# USB-Interface_V1_1.net
KiCad netlist of a schematic drawn in EAGLE
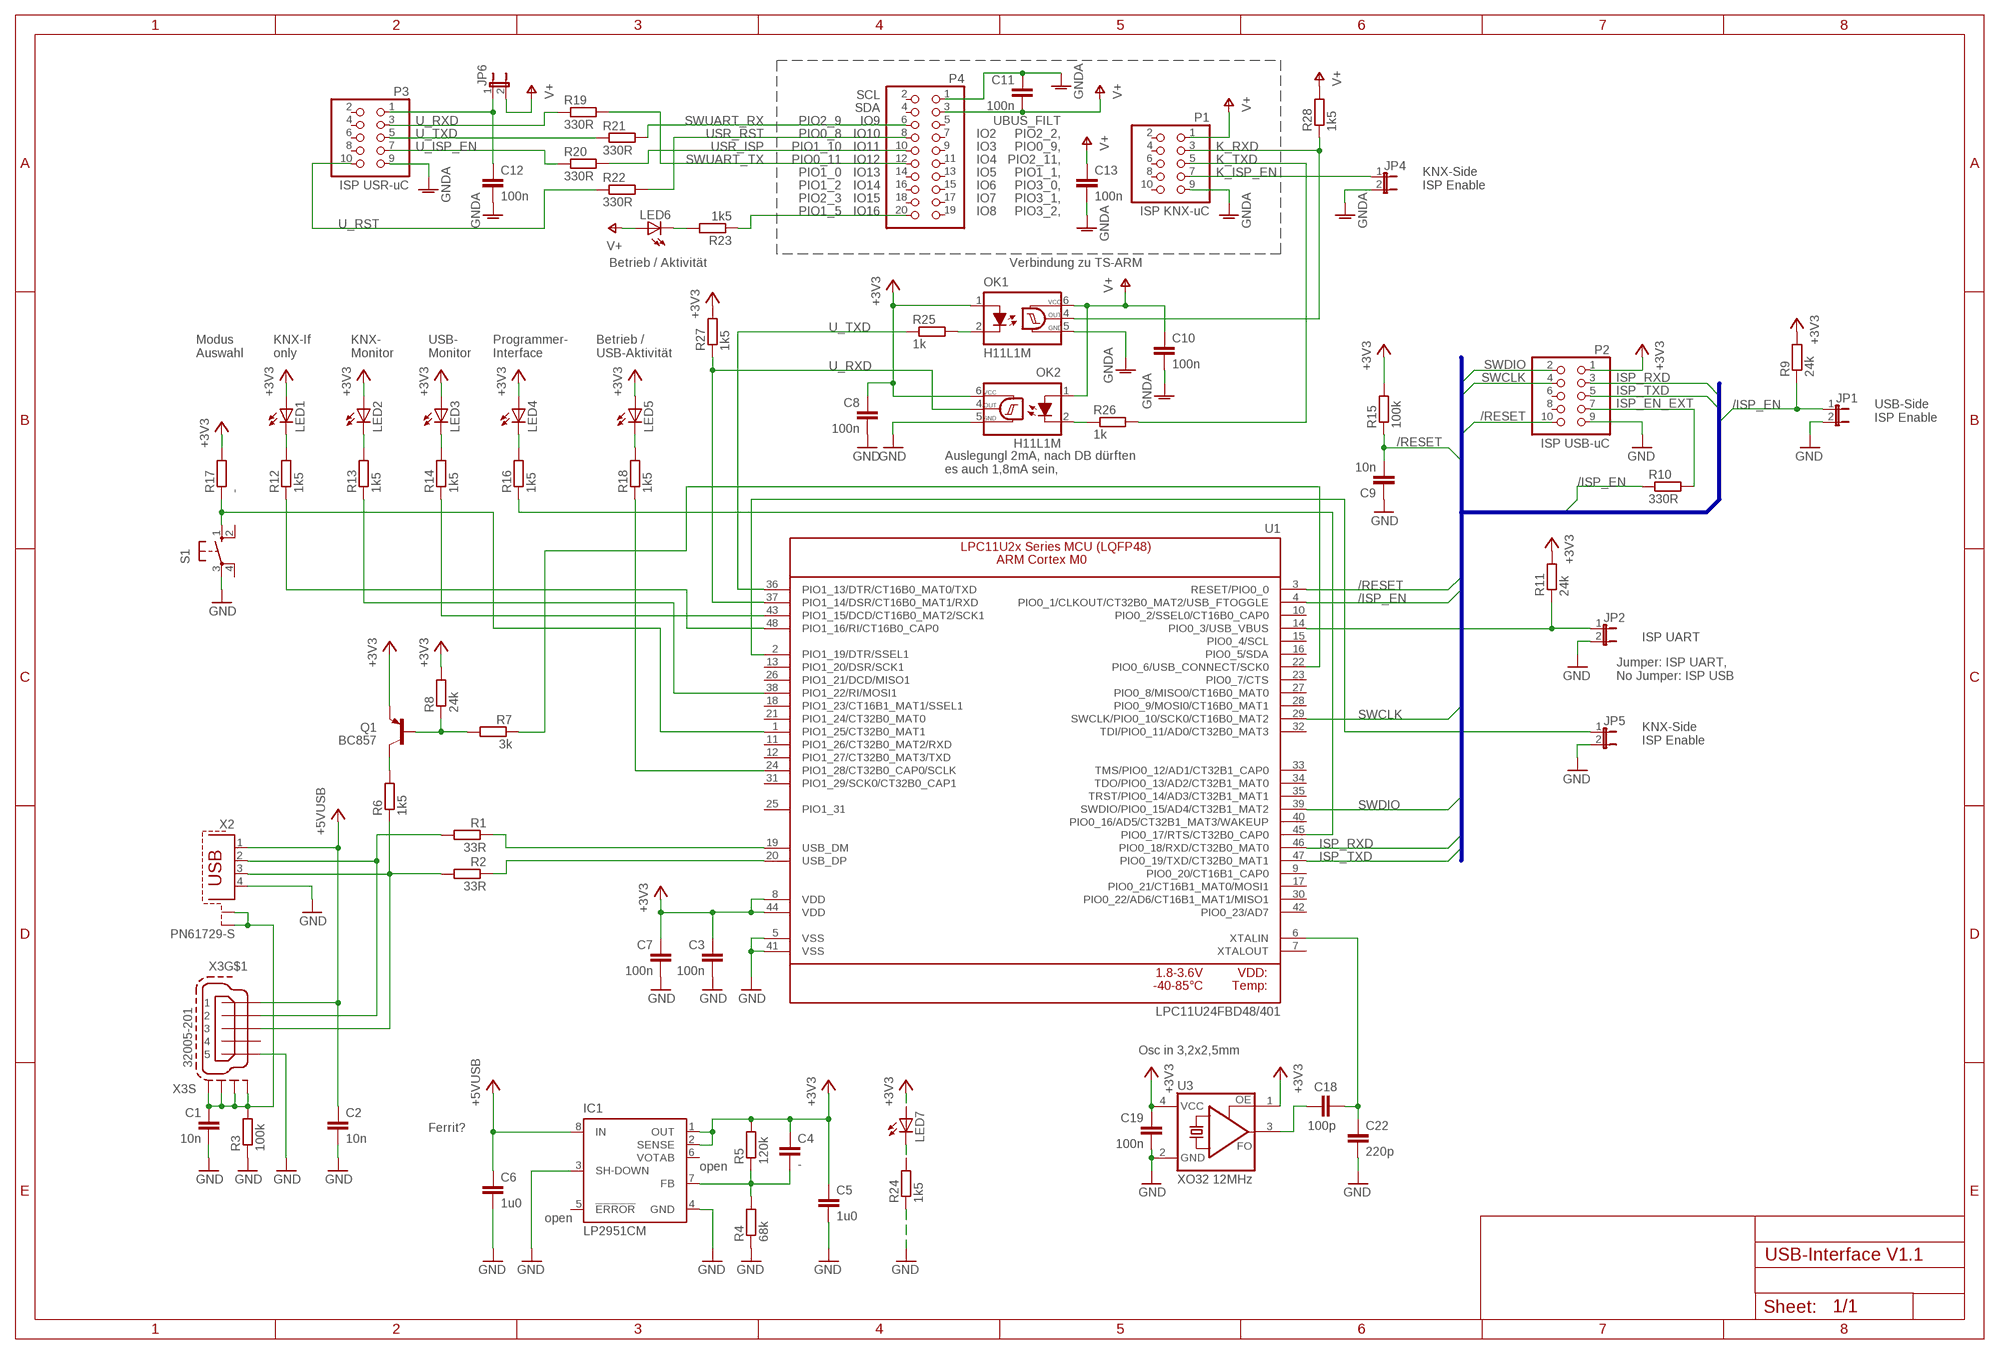
[diagram p0: schematic, sheet 1]

(export (version "E")
  (design (tool "Eeschema 10.0.6"))
  (components
    (comp (ref "C1")
      (value "10n")
      (footprint "eagle-import:R0805M")
      (libsource (lib "eagle-import") (part "C-EUC0805M"))
    )
    (comp (ref "C2")
      (value "10n")
      (footprint "eagle-import:R0805M")
      (libsource (lib "eagle-import") (part "C-EUC0805M"))
    )
    (comp (ref "C3")
      (value "100n")
      (footprint "eagle-import:R0805M")
      (libsource (lib "eagle-import") (part "C-EUC0805M"))
    )
    (comp (ref "C4")
      (value "-")
      (footprint "eagle-import:R0805M")
      (libsource (lib "eagle-import") (part "C-EUC0805M"))
    )
    (comp (ref "C5")
      (value "1u0")
      (footprint "eagle-import:R0805M")
      (libsource (lib "eagle-import") (part "C-EUC0805M"))
    )
    (comp (ref "C6")
      (value "1u0")
      (footprint "eagle-import:R0805M")
      (libsource (lib "eagle-import") (part "C-EUC0805M"))
    )
    (comp (ref "C7")
      (value "100n")
      (footprint "eagle-import:R0805M")
      (libsource (lib "eagle-import") (part "C-EUC0805M"))
    )
    (comp (ref "C8")
      (value "100n")
      (footprint "eagle-import:R0805M")
      (libsource (lib "eagle-import") (part "C-EUC0805M"))
    )
    (comp (ref "C9")
      (value "10n")
      (footprint "eagle-import:R0805M")
      (libsource (lib "eagle-import") (part "C-EUC0805M"))
    )
    (comp (ref "C10")
      (value "100n")
      (footprint "eagle-import:R0805M")
      (libsource (lib "eagle-import") (part "C-EUC0805M"))
    )
    (comp (ref "C11")
      (value "100n")
      (footprint "eagle-import:R0805M")
      (libsource (lib "eagle-import") (part "C-EUC0805M"))
    )
    (comp (ref "C12")
      (value "100n")
      (footprint "eagle-import:R0805M")
      (libsource (lib "eagle-import") (part "C-EUC0805M"))
    )
    (comp (ref "C13")
      (value "100n")
      (footprint "eagle-import:R0805M")
      (libsource (lib "eagle-import") (part "C-EUC0805M"))
    )
    (comp (ref "C18")
      (value "100p")
      (footprint "eagle-import:R0805M")
      (libsource (lib "eagle-import") (part "C-EUC0805M"))
    )
    (comp (ref "C19")
      (value "100n")
      (footprint "eagle-import:R0805M")
      (libsource (lib "eagle-import") (part "C-EUC0805M"))
    )
    (comp (ref "C22")
      (value "220p")
      (footprint "eagle-import:R0805M")
      (libsource (lib "eagle-import") (part "C-EUC0805M"))
    )
    (comp (ref "IC1")
      (value "LP2951CM")
      (footprint "eagle-import:SO08")
      (libsource (lib "eagle-import") (part "LP2951D"))
    )
    (comp (ref "JP1")
      (value "JP1E")
      (footprint "eagle-import:JP1")
      (libsource (lib "eagle-import") (part "JP1E"))
    )
    (comp (ref "JP2")
      (value "JP1E")
      (footprint "eagle-import:JP1")
      (libsource (lib "eagle-import") (part "JP1E"))
    )
    (comp (ref "JP4")
      (value "JP1E")
      (footprint "eagle-import:JP1")
      (libsource (lib "eagle-import") (part "JP1E"))
    )
    (comp (ref "JP5")
      (value "JP1E")
      (footprint "eagle-import:JP1")
      (libsource (lib "eagle-import") (part "JP1E"))
    )
    (comp (ref "JP6")
      (value "JP1E")
      (footprint "eagle-import:JP1")
      (libsource (lib "eagle-import") (part "JP1E"))
    )
    (comp (ref "LED1")
      (value "LEDSMT1206")
      (footprint "eagle-import:1206")
      (libsource (lib "eagle-import") (part "LEDSMT1206"))
    )
    (comp (ref "LED2")
      (value "LEDSMT1206")
      (footprint "eagle-import:1206")
      (libsource (lib "eagle-import") (part "LEDSMT1206"))
    )
    (comp (ref "LED3")
      (value "LEDSMT1206")
      (footprint "eagle-import:1206")
      (libsource (lib "eagle-import") (part "LEDSMT1206"))
    )
    (comp (ref "LED4")
      (value "LEDSMT1206")
      (footprint "eagle-import:1206")
      (libsource (lib "eagle-import") (part "LEDSMT1206"))
    )
    (comp (ref "LED5")
      (value "LEDSMT1206")
      (footprint "eagle-import:1206")
      (libsource (lib "eagle-import") (part "LEDSMT1206"))
    )
    (comp (ref "LED6")
      (value "LEDSMT1206")
      (footprint "eagle-import:1206")
      (libsource (lib "eagle-import") (part "LEDSMT1206"))
    )
    (comp (ref "LED7")
      (value "LEDSMT1206")
      (footprint "eagle-import:1206")
      (libsource (lib "eagle-import") (part "LEDSMT1206"))
    )
    (comp (ref "OK1")
      (value "H11L1M")
      (footprint "eagle-import:DIL06S")
      (libsource (lib "eagle-import") (part "H11LMM"))
    )
    (comp (ref "OK2")
      (value "H11L1M")
      (footprint "eagle-import:DIL06S")
      (libsource (lib "eagle-import") (part "H11LMM"))
    )
    (comp (ref "P1")
      (value "ISP KNX-uC")
      (footprint "eagle-import:2X05M")
      (libsource (lib "eagle-import") (part "PINHD-2X05_2.00"))
    )
    (comp (ref "P2")
      (value "ISP USB-uC")
      (footprint "eagle-import:2X05M")
      (libsource (lib "eagle-import") (part "PINHD-2X05_2.00"))
    )
    (comp (ref "P3")
      (value "ISP USR-uC")
      (footprint "eagle-import:2X05M")
      (libsource (lib "eagle-import") (part "PINHD-2X05_2.00"))
    )
    (comp (ref "P4")
      (value "PINHD-2X10/90")
      (footprint "eagle-import:2X10_90")
      (libsource (lib "eagle-import") (part "PINHD-2X10/90"))
    )
    (comp (ref "Q1")
      (value "BC857")
      (footprint "eagle-import:SOT23-BEC")
      (libsource (lib "eagle-import") (part "BC857SMDA"))
    )
    (comp (ref "R1")
      (value "33R")
      (footprint "eagle-import:R0805M")
      (libsource (lib "eagle-import") (part "R-EU_R0805M"))
    )
    (comp (ref "R2")
      (value "33R")
      (footprint "eagle-import:R0805M")
      (libsource (lib "eagle-import") (part "R-EU_R0805M"))
    )
    (comp (ref "R3")
      (value "100k")
      (footprint "eagle-import:R0805M")
      (libsource (lib "eagle-import") (part "R-EU_R0805M"))
    )
    (comp (ref "R4")
      (value "68k")
      (footprint "eagle-import:R0805M")
      (libsource (lib "eagle-import") (part "R-EU_R0805M"))
    )
    (comp (ref "R5")
      (value "120k")
      (footprint "eagle-import:R0805M")
      (libsource (lib "eagle-import") (part "R-EU_R0805M"))
    )
    (comp (ref "R6")
      (value "1k5")
      (footprint "eagle-import:R0805M")
      (libsource (lib "eagle-import") (part "R-EU_R0805M"))
    )
    (comp (ref "R7")
      (value "3k")
      (footprint "eagle-import:R0805M")
      (libsource (lib "eagle-import") (part "R-EU_R0805M"))
    )
    (comp (ref "R8")
      (value "24k")
      (footprint "eagle-import:R0805M")
      (libsource (lib "eagle-import") (part "R-EU_R0805M"))
    )
    (comp (ref "R9")
      (value "24k")
      (footprint "eagle-import:R0805M")
      (libsource (lib "eagle-import") (part "R-EU_R0805M"))
    )
    (comp (ref "R10")
      (value "330R")
      (footprint "eagle-import:R0805M")
      (libsource (lib "eagle-import") (part "R-EU_R0805M"))
    )
    (comp (ref "R11")
      (value "24k")
      (footprint "eagle-import:R0805M")
      (libsource (lib "eagle-import") (part "R-EU_R0805M"))
    )
    (comp (ref "R12")
      (value "1k5")
      (footprint "eagle-import:R0805M")
      (libsource (lib "eagle-import") (part "R-EU_R0805M"))
    )
    (comp (ref "R13")
      (value "1k5")
      (footprint "eagle-import:R0805M")
      (libsource (lib "eagle-import") (part "R-EU_R0805M"))
    )
    (comp (ref "R14")
      (value "1k5")
      (footprint "eagle-import:R0805M")
      (libsource (lib "eagle-import") (part "R-EU_R0805M"))
    )
    (comp (ref "R15")
      (value "100k")
      (footprint "eagle-import:R0805M")
      (libsource (lib "eagle-import") (part "R-EU_R0805M"))
    )
    (comp (ref "R16")
      (value "1k5")
      (footprint "eagle-import:R0805M")
      (libsource (lib "eagle-import") (part "R-EU_R0805M"))
    )
    (comp (ref "R17")
      (value "-")
      (footprint "eagle-import:R0805M")
      (libsource (lib "eagle-import") (part "R-EU_R0805M"))
    )
    (comp (ref "R18")
      (value "1k5")
      (footprint "eagle-import:R0805M")
      (libsource (lib "eagle-import") (part "R-EU_R0805M"))
    )
    (comp (ref "R19")
      (value "330R")
      (footprint "eagle-import:R0805M")
      (libsource (lib "eagle-import") (part "R-EU_R0805M"))
    )
    (comp (ref "R20")
      (value "330R")
      (footprint "eagle-import:R0805M")
      (libsource (lib "eagle-import") (part "R-EU_R0805M"))
    )
    (comp (ref "R21")
      (value "330R")
      (footprint "eagle-import:R0805M")
      (libsource (lib "eagle-import") (part "R-EU_R0805M"))
    )
    (comp (ref "R22")
      (value "330R")
      (footprint "eagle-import:R0805M")
      (libsource (lib "eagle-import") (part "R-EU_R0805M"))
    )
    (comp (ref "R23")
      (value "1k5")
      (footprint "eagle-import:R0805M")
      (libsource (lib "eagle-import") (part "R-EU_R0805M"))
    )
    (comp (ref "R24")
      (value "1k5")
      (footprint "eagle-import:R0805M")
      (libsource (lib "eagle-import") (part "R-EU_R0805M"))
    )
    (comp (ref "R25")
      (value "1k")
      (footprint "eagle-import:R0805M")
      (libsource (lib "eagle-import") (part "R-EU_R0805M"))
    )
    (comp (ref "R26")
      (value "1k")
      (footprint "eagle-import:R0805M")
      (libsource (lib "eagle-import") (part "R-EU_R0805M"))
    )
    (comp (ref "R27")
      (value "1k5")
      (footprint "eagle-import:R0805M")
      (libsource (lib "eagle-import") (part "R-EU_R0805M"))
    )
    (comp (ref "R28")
      (value "1k5")
      (footprint "eagle-import:R0805M")
      (libsource (lib "eagle-import") (part "R-EU_R0805M"))
    )
    (comp (ref "S1")
      (value "10-XXSMD")
      (footprint "eagle-import:B3F-10XX_SMD")
      (libsource (lib "eagle-import") (part "10-XXSMD"))
    )
    (comp (ref "U1")
      (value "LPC11U24FBD48/401")
      (footprint "eagle-import:LQFP48")
      (libsource (lib "eagle-import") (part "LPC11U24FBD48"))
    )
    (comp (ref "U3")
      (value "XO32 12MHz")
      (footprint "eagle-import:ASF")
      (libsource (lib "eagle-import") (part "ASFL"))
    )
    (comp (ref "X2")
      (value "PN61729-S")
      (footprint "eagle-import:PN61729-S")
      (libsource (lib "eagle-import") (part "PN61729-S"))
    )
    (comp (ref "X3")
      (value "32005-201")
      (footprint "eagle-import:32005-201")
      (libsource (lib "eagle-import") (part "MINI-USB-SCHIELD-32005-201"))
    )
  )
  (nets
    (net (code "1") (name "+3V3") (class "Default")
      (node (ref "C19") (pin "1") (pinfunction "1_1") (pintype "passive"))
      (node (ref "C3") (pin "1") (pinfunction "1_1") (pintype "passive"))
      (node (ref "C4") (pin "1") (pinfunction "1_1") (pintype "passive"))
      (node (ref "C5") (pin "1") (pinfunction "1_1") (pintype "passive"))
      (node (ref "C7") (pin "1") (pinfunction "1_1") (pintype "passive"))
      (node (ref "C8") (pin "1") (pinfunction "1_1") (pintype "passive"))
      (node (ref "IC1") (pin "1") (pinfunction "OUT_1") (pintype "input"))
      (node (ref "IC1") (pin "2") (pinfunction "SENSE_2") (pintype "input"))
      (node (ref "LED1") (pin "A") (pinfunction "A_A") (pintype "passive"))
      (node (ref "LED2") (pin "A") (pinfunction "A_A") (pintype "passive"))
      (node (ref "LED3") (pin "A") (pinfunction "A_A") (pintype "passive"))
      (node (ref "LED4") (pin "A") (pinfunction "A_A") (pintype "passive"))
      (node (ref "LED5") (pin "A") (pinfunction "A_A") (pintype "passive"))
      (node (ref "LED7") (pin "A") (pinfunction "A_A") (pintype "passive"))
      (node (ref "OK1") (pin "1") (pinfunction "A_1") (pintype "passive"))
      (node (ref "OK2") (pin "6") (pinfunction "VCC_6") (pintype "power_in"))
      (node (ref "P2") (pin "1") (pinfunction "1_1") (pintype "passive"))
      (node (ref "Q1") (pin "E") (pinfunction "E_E") (pintype "passive"))
      (node (ref "R11") (pin "2") (pinfunction "2_2") (pintype "passive"))
      (node (ref "R15") (pin "2") (pinfunction "2_2") (pintype "passive"))
      (node (ref "R17") (pin "2") (pinfunction "2_2") (pintype "passive"))
      (node (ref "R27") (pin "2") (pinfunction "2_2") (pintype "passive"))
      (node (ref "R5") (pin "2") (pinfunction "2_2") (pintype "passive"))
      (node (ref "R8") (pin "2") (pinfunction "2_2") (pintype "passive"))
      (node (ref "R9") (pin "2") (pinfunction "2_2") (pintype "passive"))
      (node (ref "U1") (pin "44") (pinfunction "VDD_44") (pintype "power_in"))
      (node (ref "U1") (pin "8") (pinfunction "VDD_8") (pintype "power_in"))
      (node (ref "U3") (pin "1") (pinfunction "OE_1") (pintype "input"))
      (node (ref "U3") (pin "4") (pinfunction "VCC_4") (pintype "power_in"))
    )
    (net (code "2") (name "+5VUSB") (class "Default")
      (node (ref "C2") (pin "1") (pinfunction "1_1") (pintype "passive"))
      (node (ref "C6") (pin "1") (pinfunction "1_1") (pintype "passive"))
      (node (ref "IC1") (pin "8") (pinfunction "IN_8") (pintype "input"))
      (node (ref "X2") (pin "1") (pinfunction "1_1") (pintype "passive"))
      (node (ref "X3") (pin "1") (pinfunction "1_1") (pintype "passive"))
    )
    (net (code "3") (name "/ISP_EN_EXT") (class "Default")
      (node (ref "P2") (pin "7") (pinfunction "7_7") (pintype "passive"))
      (node (ref "R10") (pin "2") (pinfunction "2_2") (pintype "passive"))
    )
    (net (code "4") (name "/ISP_RXD") (class "Default")
      (node (ref "P2") (pin "3") (pinfunction "3_3") (pintype "passive"))
      (node (ref "U1") (pin "46") (pinfunction "PIO0_18/RXD/CT32B0_MAT0_46") (pintype "bidirectional"))
    )
    (net (code "5") (name "/ISP_TXD") (class "Default")
      (node (ref "P2") (pin "5") (pinfunction "5_5") (pintype "passive"))
      (node (ref "U1") (pin "47") (pinfunction "PIO0_19/TXD/CT32B0_MAT1_47") (pintype "bidirectional"))
    )
    (net (code "6") (name "/K_ISP_EN") (class "Default")
      (node (ref "JP4") (pin "1") (pinfunction "1_1") (pintype "passive"))
      (node (ref "P1") (pin "7") (pinfunction "7_7") (pintype "passive"))
    )
    (net (code "7") (name "/K_RXD") (class "Default")
      (node (ref "OK1") (pin "4") (pinfunction "OUT_4") (pintype "output"))
      (node (ref "P1") (pin "3") (pinfunction "3_3") (pintype "passive"))
      (node (ref "R28") (pin "1") (pinfunction "1_1") (pintype "passive"))
    )
    (net (code "8") (name "/K_TXD") (class "Default")
      (node (ref "P1") (pin "5") (pinfunction "5_5") (pintype "passive"))
      (node (ref "R26") (pin "2") (pinfunction "2_2") (pintype "passive"))
    )
    (net (code "9") (name "/SWCLK") (class "Default")
      (node (ref "P2") (pin "4") (pinfunction "4_4") (pintype "passive"))
      (node (ref "U1") (pin "29") (pinfunction "SWCLK/PIO0_10/SCK0/CT16B0_MAT2_29") (pintype "bidirectional"))
    )
    (net (code "10") (name "/SWDIO") (class "Default")
      (node (ref "P2") (pin "2") (pinfunction "2_2") (pintype "passive"))
      (node (ref "U1") (pin "39") (pinfunction "SWDIO/PIO0_15/AD4/CT32B1_MAT2_39") (pintype "bidirectional"))
    )
    (net (code "11") (name "/SWUART_RX") (class "Default")
      (node (ref "P4") (pin "6") (pinfunction "6_6") (pintype "passive"))
      (node (ref "R21") (pin "2") (pinfunction "2_2") (pintype "passive"))
    )
    (net (code "12") (name "/SWUART_TX") (class "Default")
      (node (ref "P4") (pin "12") (pinfunction "12_12") (pintype "passive"))
      (node (ref "R19") (pin "2") (pinfunction "2_2") (pintype "passive"))
    )
    (net (code "13") (name "/USR_ISP") (class "Default")
      (node (ref "P4") (pin "10") (pinfunction "10_10") (pintype "passive"))
      (node (ref "R20") (pin "2") (pinfunction "2_2") (pintype "passive"))
    )
    (net (code "14") (name "/USR_RST") (class "Default")
      (node (ref "P4") (pin "8") (pinfunction "8_8") (pintype "passive"))
      (node (ref "R22") (pin "2") (pinfunction "2_2") (pintype "passive"))
    )
    (net (code "15") (name "/U_RXD") (class "Default")
      (node (ref "OK2") (pin "4") (pinfunction "OUT_4") (pintype "output"))
      (node (ref "R27") (pin "1") (pinfunction "1_1") (pintype "passive"))
      (node (ref "U1") (pin "37") (pinfunction "PIO1_14/DSR/CT16B0_MAT1/RXD_37") (pintype "bidirectional"))
    )
    (net (code "16") (name "/U_TXD") (class "Default")
      (node (ref "R25") (pin "1") (pinfunction "1_1") (pintype "passive"))
      (node (ref "U1") (pin "36") (pinfunction "PIO1_13/DTR/CT16B0_MAT0/TXD_36") (pintype "bidirectional"))
    )
    (net (code "17") (name "/{slash}ISP_EN") (class "Default")
      (node (ref "JP1") (pin "1") (pinfunction "1_1") (pintype "passive"))
      (node (ref "R10") (pin "1") (pinfunction "1_1") (pintype "passive"))
      (node (ref "R9") (pin "1") (pinfunction "1_1") (pintype "passive"))
      (node (ref "U1") (pin "4") (pinfunction "PIO0_1/CLKOUT/CT32B0_MAT2/USB_FTOGGLE_4") (pintype "bidirectional"))
    )
    (net (code "18") (name "/{slash}RESET") (class "Default")
      (node (ref "C9") (pin "2") (pinfunction "2_2") (pintype "passive"))
      (node (ref "P2") (pin "10") (pinfunction "10_10") (pintype "passive"))
      (node (ref "R15") (pin "1") (pinfunction "1_1") (pintype "passive"))
      (node (ref "U1") (pin "3") (pinfunction "RESET/PIO0_0_3") (pintype "bidirectional"))
    )
    (net (code "19") (name "GND") (class "Default")
      (node (ref "C1") (pin "2") (pinfunction "2_2") (pintype "passive"))
      (node (ref "C19") (pin "2") (pinfunction "2_2") (pintype "passive"))
      (node (ref "C2") (pin "2") (pinfunction "2_2") (pintype "passive"))
      (node (ref "C22") (pin "2") (pinfunction "2_2") (pintype "passive"))
      (node (ref "C3") (pin "2") (pinfunction "2_2") (pintype "passive"))
      (node (ref "C5") (pin "2") (pinfunction "2_2") (pintype "passive"))
      (node (ref "C6") (pin "2") (pinfunction "2_2") (pintype "passive"))
      (node (ref "C7") (pin "2") (pinfunction "2_2") (pintype "passive"))
      (node (ref "C8") (pin "2") (pinfunction "2_2") (pintype "passive"))
      (node (ref "C9") (pin "1") (pinfunction "1_1") (pintype "passive"))
      (node (ref "IC1") (pin "3") (pinfunction "SH-DOWN_3") (pintype "input"))
      (node (ref "IC1") (pin "4") (pinfunction "GND_4") (pintype "power_in"))
      (node (ref "JP1") (pin "2") (pinfunction "2_2") (pintype "passive"))
      (node (ref "JP2") (pin "2") (pinfunction "2_2") (pintype "passive"))
      (node (ref "JP5") (pin "2") (pinfunction "2_2") (pintype "passive"))
      (node (ref "OK2") (pin "5") (pinfunction "GND_5") (pintype "power_in"))
      (node (ref "P2") (pin "9") (pinfunction "9_9") (pintype "passive"))
      (node (ref "R24") (pin "1") (pinfunction "1_1") (pintype "passive"))
      (node (ref "R3") (pin "1") (pinfunction "1_1") (pintype "passive"))
      (node (ref "R4") (pin "1") (pinfunction "1_1") (pintype "passive"))
      (node (ref "S1") (pin "3") (pinfunction "P_3") (pintype "passive"))
      (node (ref "U1") (pin "41") (pinfunction "VSS_41") (pintype "power_in"))
      (node (ref "U1") (pin "5") (pinfunction "VSS_5") (pintype "power_in"))
      (node (ref "U3") (pin "2") (pinfunction "GND_2") (pintype "power_in"))
      (node (ref "X2") (pin "4") (pinfunction "4_4") (pintype "passive"))
      (node (ref "X3") (pin "5") (pinfunction "5_5") (pintype "passive"))
    )
    (net (code "20") (name "GNDA") (class "Default")
      (node (ref "C10") (pin "2") (pinfunction "2_2") (pintype "passive"))
      (node (ref "C11") (pin "1") (pinfunction "1_1") (pintype "passive"))
      (node (ref "C12") (pin "2") (pinfunction "2_2") (pintype "passive"))
      (node (ref "C13") (pin "2") (pinfunction "2_2") (pintype "passive"))
      (node (ref "JP4") (pin "2") (pinfunction "2_2") (pintype "passive"))
      (node (ref "OK1") (pin "5") (pinfunction "GND_5") (pintype "power_in"))
      (node (ref "P1") (pin "9") (pinfunction "9_9") (pintype "passive"))
      (node (ref "P3") (pin "9") (pinfunction "9_9") (pintype "passive"))
      (node (ref "P4") (pin "1") (pinfunction "1_1") (pintype "passive"))
    )
    (net (code "21") (name "Net-(C12-Pad1)") (class "Default")
      (node (ref "C12") (pin "1") (pinfunction "1_1") (pintype "passive"))
      (node (ref "JP6") (pin "1") (pinfunction "1_1") (pintype "passive"))
      (node (ref "P3") (pin "1") (pinfunction "1_1") (pintype "passive"))
    )
    (net (code "22") (name "Net-(IC1-FB)") (class "Default")
      (node (ref "C4") (pin "2") (pinfunction "2_2") (pintype "passive"))
      (node (ref "IC1") (pin "7") (pinfunction "FB_7") (pintype "input"))
      (node (ref "R4") (pin "2") (pinfunction "2_2") (pintype "passive"))
      (node (ref "R5") (pin "1") (pinfunction "1_1") (pintype "passive"))
    )
    (net (code "23") (name "Net-(LED1-PadC)") (class "Default")
      (node (ref "LED1") (pin "C") (pinfunction "C_C") (pintype "passive"))
      (node (ref "R12") (pin "2") (pinfunction "2_2") (pintype "passive"))
    )
    (net (code "24") (name "Net-(LED2-PadC)") (class "Default")
      (node (ref "LED2") (pin "C") (pinfunction "C_C") (pintype "passive"))
      (node (ref "R13") (pin "2") (pinfunction "2_2") (pintype "passive"))
    )
    (net (code "25") (name "Net-(LED3-PadC)") (class "Default")
      (node (ref "LED3") (pin "C") (pinfunction "C_C") (pintype "passive"))
      (node (ref "R14") (pin "2") (pinfunction "2_2") (pintype "passive"))
    )
    (net (code "26") (name "Net-(LED4-PadC)") (class "Default")
      (node (ref "LED4") (pin "C") (pinfunction "C_C") (pintype "passive"))
      (node (ref "R16") (pin "2") (pinfunction "2_2") (pintype "passive"))
    )
    (net (code "27") (name "Net-(LED5-PadC)") (class "Default")
      (node (ref "LED5") (pin "C") (pinfunction "C_C") (pintype "passive"))
      (node (ref "R18") (pin "2") (pinfunction "2_2") (pintype "passive"))
    )
    (net (code "28") (name "Net-(LED6-PadC)") (class "Default")
      (node (ref "LED6") (pin "C") (pinfunction "C_C") (pintype "passive"))
      (node (ref "R23") (pin "2") (pinfunction "2_2") (pintype "passive"))
    )
    (net (code "29") (name "Net-(LED7-PadC)") (class "Default")
      (node (ref "LED7") (pin "C") (pinfunction "C_C") (pintype "passive"))
      (node (ref "R24") (pin "2") (pinfunction "2_2") (pintype "passive"))
    )
    (net (code "30") (name "Net-(OK1-C)") (class "Default")
      (node (ref "OK1") (pin "2") (pinfunction "C_2") (pintype "passive"))
      (node (ref "R25") (pin "2") (pinfunction "2_2") (pintype "passive"))
    )
    (net (code "31") (name "Net-(OK2-C)") (class "Default")
      (node (ref "OK2") (pin "2") (pinfunction "C_2") (pintype "passive"))
      (node (ref "R26") (pin "1") (pinfunction "1_1") (pintype "passive"))
    )
    (net (code "32") (name "Net-(P3-Pad3)") (class "Default")
      (node (ref "P3") (pin "3") (pinfunction "3_3") (pintype "passive"))
      (node (ref "R19") (pin "1") (pinfunction "1_1") (pintype "passive"))
    )
    (net (code "33") (name "Net-(P3-Pad5)") (class "Default")
      (node (ref "P3") (pin "5") (pinfunction "5_5") (pintype "passive"))
      (node (ref "R21") (pin "1") (pinfunction "1_1") (pintype "passive"))
    )
    (net (code "34") (name "Net-(P3-Pad7)") (class "Default")
      (node (ref "P3") (pin "7") (pinfunction "7_7") (pintype "passive"))
      (node (ref "R20") (pin "1") (pinfunction "1_1") (pintype "passive"))
    )
    (net (code "35") (name "Net-(P3-Pad10)") (class "Default")
      (node (ref "P3") (pin "10") (pinfunction "10_10") (pintype "passive"))
      (node (ref "R22") (pin "1") (pinfunction "1_1") (pintype "passive"))
    )
    (net (code "36") (name "Net-(P4-Pad20)") (class "Default")
      (node (ref "P4") (pin "20") (pinfunction "20_20") (pintype "passive"))
      (node (ref "R23") (pin "1") (pinfunction "1_1") (pintype "passive"))
    )
    (net (code "37") (name "Net-(Q1-PadB)") (class "Default")
      (node (ref "Q1") (pin "B") (pinfunction "B_B") (pintype "passive"))
      (node (ref "R7") (pin "2") (pinfunction "2_2") (pintype "passive"))
      (node (ref "R8") (pin "1") (pinfunction "1_1") (pintype "passive"))
    )
    (net (code "38") (name "Net-(Q1-PadC)") (class "Default")
      (node (ref "Q1") (pin "C") (pinfunction "C_C") (pintype "passive"))
      (node (ref "R6") (pin "2") (pinfunction "2_2") (pintype "passive"))
    )
    (net (code "39") (name "Net-(R1-Pad2)") (class "Default")
      (node (ref "R1") (pin "2") (pinfunction "2_2") (pintype "passive"))
      (node (ref "X2") (pin "2") (pinfunction "2_2") (pintype "passive"))
      (node (ref "X3") (pin "2") (pinfunction "2_2") (pintype "passive"))
    )
    (net (code "40") (name "Net-(R2-Pad2)") (class "Default")
      (node (ref "R2") (pin "2") (pinfunction "2_2") (pintype "passive"))
      (node (ref "R6") (pin "1") (pinfunction "1_1") (pintype "passive"))
      (node (ref "X2") (pin "3") (pinfunction "3_3") (pintype "passive"))
      (node (ref "X3") (pin "3") (pinfunction "3_3") (pintype "passive"))
    )
    (net (code "41") (name "Net-(S1-S)") (class "Default")
      (node (ref "R17") (pin "1") (pinfunction "1_1") (pintype "passive"))
      (node (ref "S1") (pin "1") (pinfunction "S_1") (pintype "passive"))
      (node (ref "U1") (pin "1") (pinfunction "PIO1_25/CT32B0_MAT1_1") (pintype "bidirectional"))
    )
    (net (code "42") (name "Net-(U1-PIO0_3{slash}USB_VBUS)") (class "Default")
      (node (ref "JP2") (pin "1") (pinfunction "1_1") (pintype "passive"))
      (node (ref "R11") (pin "1") (pinfunction "1_1") (pintype "passive"))
      (node (ref "U1") (pin "14") (pinfunction "PIO0_3/USB_VBUS_14") (pintype "bidirectional"))
    )
    (net (code "43") (name "Net-(U1-PIO0_6{slash}USB_CONNECT{slash}SCK0)") (class "Default")
      (node (ref "R7") (pin "1") (pinfunction "1_1") (pintype "passive"))
      (node (ref "U1") (pin "22") (pinfunction "PIO0_6/USB_CONNECT/SCK0_22") (pintype "bidirectional"))
    )
    (net (code "44") (name "Net-(U1-PIO0_17{slash}RTS{slash}CT32B0_CAP0)") (class "Default")
      (node (ref "R16") (pin "1") (pinfunction "1_1") (pintype "passive"))
      (node (ref "U1") (pin "45") (pinfunction "PIO0_17/RTS/CT32B0_CAP0_45") (pintype "bidirectional"))
    )
    (net (code "45") (name "Net-(U1-PIO1_15{slash}DCD{slash}CT16B0_MAT2{slash}SCK1)") (class "Default")
      (node (ref "R14") (pin "1") (pinfunction "1_1") (pintype "passive"))
      (node (ref "U1") (pin "43") (pinfunction "PIO1_15/DCD/CT16B0_MAT2/SCK1_43") (pintype "bidirectional"))
    )
    (net (code "46") (name "Net-(U1-PIO1_16{slash}RI{slash}CT16B0_CAP0)") (class "Default")
      (node (ref "R12") (pin "1") (pinfunction "1_1") (pintype "passive"))
      (node (ref "U1") (pin "48") (pinfunction "PIO1_16/RI/CT16B0_CAP0_48") (pintype "bidirectional"))
    )
    (net (code "47") (name "Net-(U1-PIO1_19{slash}DTR{slash}SSEL1)") (class "Default")
      (node (ref "JP5") (pin "1") (pinfunction "1_1") (pintype "passive"))
      (node (ref "U1") (pin "2") (pinfunction "PIO1_19/DTR/SSEL1_2") (pintype "bidirectional"))
    )
    (net (code "48") (name "Net-(U1-PIO1_22{slash}RI{slash}MOSI1)") (class "Default")
      (node (ref "R13") (pin "1") (pinfunction "1_1") (pintype "passive"))
      (node (ref "U1") (pin "38") (pinfunction "PIO1_22/RI/MOSI1_38") (pintype "bidirectional"))
    )
    (net (code "49") (name "Net-(U1-PIO1_28{slash}CT32B0_CAP0{slash}SCLK)") (class "Default")
      (node (ref "R18") (pin "1") (pinfunction "1_1") (pintype "passive"))
      (node (ref "U1") (pin "24") (pinfunction "PIO1_28/CT32B0_CAP0/SCLK_24") (pintype "bidirectional"))
    )
    (net (code "50") (name "Net-(U1-USB_DM)") (class "Default")
      (node (ref "R1") (pin "1") (pinfunction "1_1") (pintype "passive"))
      (node (ref "U1") (pin "19") (pinfunction "USB_DM_19") (pintype "bidirectional"))
    )
    (net (code "51") (name "Net-(U1-USB_DP)") (class "Default")
      (node (ref "R2") (pin "1") (pinfunction "1_1") (pintype "passive"))
      (node (ref "U1") (pin "20") (pinfunction "USB_DP_20") (pintype "bidirectional"))
    )
    (net (code "52") (name "Net-(U1-XTALIN)") (class "Default")
      (node (ref "C18") (pin "2") (pinfunction "2_2") (pintype "passive"))
      (node (ref "C22") (pin "1") (pinfunction "1_1") (pintype "passive"))
      (node (ref "U1") (pin "6") (pinfunction "XTALIN_6") (pintype "input"))
    )
    (net (code "53") (name "Net-(U3-FO)") (class "Default")
      (node (ref "C18") (pin "1") (pinfunction "1_1") (pintype "passive"))
      (node (ref "U3") (pin "3") (pinfunction "FO_3") (pintype "output"))
    )
    (net (code "54") (name "Net-(X3B-S1)") (class "Default")
      (node (ref "C1") (pin "1") (pinfunction "1_1") (pintype "passive"))
      (node (ref "R3") (pin "2") (pinfunction "2_2") (pintype "passive"))
      (node (ref "X2") (pin "S1") (pinfunction "S1_S1") (pintype "passive"))
      (node (ref "X2") (pin "S2") (pinfunction "S2_S2") (pintype "passive"))
      (node (ref "X3") (pin "M1") (pinfunction "S1_M1") (pintype "passive"))
      (node (ref "X3") (pin "M2") (pinfunction "S2_M2") (pintype "passive"))
      (node (ref "X3") (pin "M3") (pinfunction "S3_M3") (pintype "passive"))
      (node (ref "X3") (pin "M4") (pinfunction "S4_M4") (pintype "passive"))
    )
    (net (code "55") (name "V+") (class "Default")
      (node (ref "C10") (pin "1") (pinfunction "1_1") (pintype "passive"))
      (node (ref "C11") (pin "2") (pinfunction "2_2") (pintype "passive"))
      (node (ref "C13") (pin "1") (pinfunction "1_1") (pintype "passive"))
      (node (ref "JP6") (pin "2") (pinfunction "2_2") (pintype "passive"))
      (node (ref "LED6") (pin "A") (pinfunction "A_A") (pintype "passive"))
      (node (ref "OK1") (pin "6") (pinfunction "VCC_6") (pintype "power_in"))
      (node (ref "OK2") (pin "1") (pinfunction "A_1") (pintype "passive"))
      (node (ref "P1") (pin "1") (pinfunction "1_1") (pintype "passive"))
      (node (ref "P4") (pin "3") (pinfunction "3_3") (pintype "passive"))
      (node (ref "R28") (pin "2") (pinfunction "2_2") (pintype "passive"))
    )
    (net (code "56") (name "unconnected-(IC1-VOTAB-Pad6)") (class "Default")
      (node (ref "IC1") (pin "6") (pinfunction "VOTAB_6") (pintype "passive"))
    )
    (net (code "57") (name "unconnected-(IC1-~{ERROR}-Pad5)") (class "Default")
      (node (ref "IC1") (pin "5") (pinfunction "~{ERROR}_5") (pintype "output"))
    )
    (net (code "58") (name "unconnected-(P1-Pad2)") (class "Default")
      (node (ref "P1") (pin "2") (pinfunction "2_2") (pintype "passive"))
    )
    (net (code "59") (name "unconnected-(P1-Pad4)") (class "Default")
      (node (ref "P1") (pin "4") (pinfunction "4_4") (pintype "passive"))
    )
    (net (code "60") (name "unconnected-(P1-Pad6)") (class "Default")
      (node (ref "P1") (pin "6") (pinfunction "6_6") (pintype "passive"))
    )
    (net (code "61") (name "unconnected-(P1-Pad8)") (class "Default")
      (node (ref "P1") (pin "8") (pinfunction "8_8") (pintype "passive"))
    )
    (net (code "62") (name "unconnected-(P1-Pad10)") (class "Default")
      (node (ref "P1") (pin "10") (pinfunction "10_10") (pintype "passive"))
    )
    (net (code "63") (name "unconnected-(P2-Pad6)") (class "Default")
      (node (ref "P2") (pin "6") (pinfunction "6_6") (pintype "passive"))
    )
    (net (code "64") (name "unconnected-(P2-Pad8)") (class "Default")
      (node (ref "P2") (pin "8") (pinfunction "8_8") (pintype "passive"))
    )
    (net (code "65") (name "unconnected-(P3-Pad2)") (class "Default")
      (node (ref "P3") (pin "2") (pinfunction "2_2") (pintype "passive"))
    )
    (net (code "66") (name "unconnected-(P3-Pad4)") (class "Default")
      (node (ref "P3") (pin "4") (pinfunction "4_4") (pintype "passive"))
    )
    (net (code "67") (name "unconnected-(P3-Pad6)") (class "Default")
      (node (ref "P3") (pin "6") (pinfunction "6_6") (pintype "passive"))
    )
    (net (code "68") (name "unconnected-(P3-Pad8)") (class "Default")
      (node (ref "P3") (pin "8") (pinfunction "8_8") (pintype "passive"))
    )
    (net (code "69") (name "unconnected-(P4-Pad2)") (class "Default")
      (node (ref "P4") (pin "2") (pinfunction "2_2") (pintype "passive"))
    )
    (net (code "70") (name "unconnected-(P4-Pad4)") (class "Default")
      (node (ref "P4") (pin "4") (pinfunction "4_4") (pintype "passive"))
    )
    (net (code "71") (name "unconnected-(P4-Pad5)") (class "Default")
      (node (ref "P4") (pin "5") (pinfunction "5_5") (pintype "passive"))
    )
    (net (code "72") (name "unconnected-(P4-Pad7)") (class "Default")
      (node (ref "P4") (pin "7") (pinfunction "7_7") (pintype "passive"))
    )
    (net (code "73") (name "unconnected-(P4-Pad9)") (class "Default")
      (node (ref "P4") (pin "9") (pinfunction "9_9") (pintype "passive"))
    )
    (net (code "74") (name "unconnected-(P4-Pad11)") (class "Default")
      (node (ref "P4") (pin "11") (pinfunction "11_11") (pintype "passive"))
    )
    (net (code "75") (name "unconnected-(P4-Pad13)") (class "Default")
      (node (ref "P4") (pin "13") (pinfunction "13_13") (pintype "passive"))
    )
    (net (code "76") (name "unconnected-(P4-Pad14)") (class "Default")
      (node (ref "P4") (pin "14") (pinfunction "14_14") (pintype "passive"))
    )
    (net (code "77") (name "unconnected-(P4-Pad15)") (class "Default")
      (node (ref "P4") (pin "15") (pinfunction "15_15") (pintype "passive"))
    )
    (net (code "78") (name "unconnected-(P4-Pad16)") (class "Default")
      (node (ref "P4") (pin "16") (pinfunction "16_16") (pintype "passive"))
    )
    (net (code "79") (name "unconnected-(P4-Pad17)") (class "Default")
      (node (ref "P4") (pin "17") (pinfunction "17_17") (pintype "passive"))
    )
    (net (code "80") (name "unconnected-(P4-Pad18)") (class "Default")
      (node (ref "P4") (pin "18") (pinfunction "18_18") (pintype "passive"))
    )
    (net (code "81") (name "unconnected-(P4-Pad19)") (class "Default")
      (node (ref "P4") (pin "19") (pinfunction "19_19") (pintype "passive"))
    )
    (net (code "82") (name "unconnected-(S1-P1-Pad4)") (class "Default")
      (node (ref "S1") (pin "4") (pinfunction "P1_4") (pintype "passive"))
    )
    (net (code "83") (name "unconnected-(S1-S1-Pad2)") (class "Default")
      (node (ref "S1") (pin "2") (pinfunction "S1_2") (pintype "passive"))
    )
    (net (code "84") (name "unconnected-(U1-PIO0_2{slash}SSEL0{slash}CT16B0_CAP0-Pad10)") (class "Default")
      (node (ref "U1") (pin "10") (pinfunction "PIO0_2/SSEL0/CT16B0_CAP0_10") (pintype "bidirectional"))
    )
    (net (code "85") (name "unconnected-(U1-PIO0_4{slash}SCL-Pad15)") (class "Default")
      (node (ref "U1") (pin "15") (pinfunction "PIO0_4/SCL_15") (pintype "bidirectional"))
    )
    (net (code "86") (name "unconnected-(U1-PIO0_5{slash}SDA-Pad16)") (class "Default")
      (node (ref "U1") (pin "16") (pinfunction "PIO0_5/SDA_16") (pintype "bidirectional"))
    )
    (net (code "87") (name "unconnected-(U1-PIO0_7{slash}CTS-Pad23)") (class "Default")
      (node (ref "U1") (pin "23") (pinfunction "PIO0_7/CTS_23") (pintype "bidirectional"))
    )
    (net (code "88") (name "unconnected-(U1-PIO0_8{slash}MISO0{slash}CT16B0_MAT0-Pad27)") (class "Default")
      (node (ref "U1") (pin "27") (pinfunction "PIO0_8/MISO0/CT16B0_MAT0_27") (pintype "bidirectional"))
    )
    (net (code "89") (name "unconnected-(U1-PIO0_9{slash}MOSI0{slash}CT16B0_MAT1-Pad28)") (class "Default")
      (node (ref "U1") (pin "28") (pinfunction "PIO0_9/MOSI0/CT16B0_MAT1_28") (pintype "bidirectional"))
    )
    (net (code "90") (name "unconnected-(U1-PIO0_16{slash}AD5{slash}CT32B1_MAT3{slash}WAKEUP-Pad40)") (class "Default")
      (node (ref "U1") (pin "40") (pinfunction "PIO0_16/AD5/CT32B1_MAT3/WAKEUP_40") (pintype "bidirectional"))
    )
    (net (code "91") (name "unconnected-(U1-PIO0_20{slash}CT16B1_CAP0-Pad9)") (class "Default")
      (node (ref "U1") (pin "9") (pinfunction "PIO0_20/CT16B1_CAP0_9") (pintype "bidirectional"))
    )
    (net (code "92") (name "unconnected-(U1-PIO0_21{slash}CT16B1_MAT0{slash}MOSI1-Pad17)") (class "Default")
      (node (ref "U1") (pin "17") (pinfunction "PIO0_21/CT16B1_MAT0/MOSI1_17") (pintype "bidirectional"))
    )
    (net (code "93") (name "unconnected-(U1-PIO0_22{slash}AD6{slash}CT16B1_MAT1{slash}MISO1-Pad30)") (class "Default")
      (node (ref "U1") (pin "30") (pinfunction "PIO0_22/AD6/CT16B1_MAT1/MISO1_30") (pintype "bidirectional"))
    )
    (net (code "94") (name "unconnected-(U1-PIO0_23{slash}AD7-Pad42)") (class "Default")
      (node (ref "U1") (pin "42") (pinfunction "PIO0_23/AD7_42") (pintype "bidirectional"))
    )
    (net (code "95") (name "unconnected-(U1-PIO1_20{slash}DSR{slash}SCK1-Pad13)") (class "Default")
      (node (ref "U1") (pin "13") (pinfunction "PIO1_20/DSR/SCK1_13") (pintype "bidirectional"))
    )
    (net (code "96") (name "unconnected-(U1-PIO1_21{slash}DCD{slash}MISO1-Pad26)") (class "Default")
      (node (ref "U1") (pin "26") (pinfunction "PIO1_21/DCD/MISO1_26") (pintype "bidirectional"))
    )
    (net (code "97") (name "unconnected-(U1-PIO1_23{slash}CT16B1_MAT1{slash}SSEL1-Pad18)") (class "Default")
      (node (ref "U1") (pin "18") (pinfunction "PIO1_23/CT16B1_MAT1/SSEL1_18") (pintype "bidirectional"))
    )
    (net (code "98") (name "unconnected-(U1-PIO1_24{slash}CT32B0_MAT0-Pad21)") (class "Default")
      (node (ref "U1") (pin "21") (pinfunction "PIO1_24/CT32B0_MAT0_21") (pintype "bidirectional"))
    )
    (net (code "99") (name "unconnected-(U1-PIO1_26{slash}CT32B0_MAT2{slash}RXD-Pad11)") (class "Default")
      (node (ref "U1") (pin "11") (pinfunction "PIO1_26/CT32B0_MAT2/RXD_11") (pintype "bidirectional"))
    )
    (net (code "100") (name "unconnected-(U1-PIO1_27{slash}CT32B0_MAT3{slash}TXD-Pad12)") (class "Default")
      (node (ref "U1") (pin "12") (pinfunction "PIO1_27/CT32B0_MAT3/TXD_12") (pintype "bidirectional"))
    )
    (net (code "101") (name "unconnected-(U1-PIO1_29{slash}SCK0{slash}CT32B0_CAP1-Pad31)") (class "Default")
      (node (ref "U1") (pin "31") (pinfunction "PIO1_29/SCK0/CT32B0_CAP1_31") (pintype "bidirectional"))
    )
    (net (code "102") (name "unconnected-(U1-PIO1_31-Pad25)") (class "Default")
      (node (ref "U1") (pin "25") (pinfunction "PIO1_31_25") (pintype "bidirectional"))
    )
    (net (code "103") (name "unconnected-(U1-TDI{slash}PIO0_11{slash}AD0{slash}CT32B0_MAT3-Pad32)") (class "Default")
      (node (ref "U1") (pin "32") (pinfunction "TDI/PIO0_11/AD0/CT32B0_MAT3_32") (pintype "bidirectional"))
    )
    (net (code "104") (name "unconnected-(U1-TDO{slash}PIO0_13{slash}AD2{slash}CT32B1_MAT0-Pad34)") (class "Default")
      (node (ref "U1") (pin "34") (pinfunction "TDO/PIO0_13/AD2/CT32B1_MAT0_34") (pintype "bidirectional"))
    )
    (net (code "105") (name "unconnected-(U1-TMS{slash}PIO0_12{slash}AD1{slash}CT32B1_CAP0-Pad33)") (class "Default")
      (node (ref "U1") (pin "33") (pinfunction "TMS/PIO0_12/AD1/CT32B1_CAP0_33") (pintype "bidirectional"))
    )
    (net (code "106") (name "unconnected-(U1-TRST{slash}PIO0_14{slash}AD3{slash}CT32B1_MAT1-Pad35)") (class "Default")
      (node (ref "U1") (pin "35") (pinfunction "TRST/PIO0_14/AD3/CT32B1_MAT1_35") (pintype "bidirectional"))
    )
    (net (code "107") (name "unconnected-(U1-XTALOUT-Pad7)") (class "Default")
      (node (ref "U1") (pin "7") (pinfunction "XTALOUT_7") (pintype "output"))
    )
    (net (code "108") (name "unconnected-(X3-Pad4)") (class "Default")
      (node (ref "X3") (pin "4") (pinfunction "4_4") (pintype "passive"))
    )
  )
)
